# design.net
KiCad netlist of a schematic drawn in EasyEDA Pro
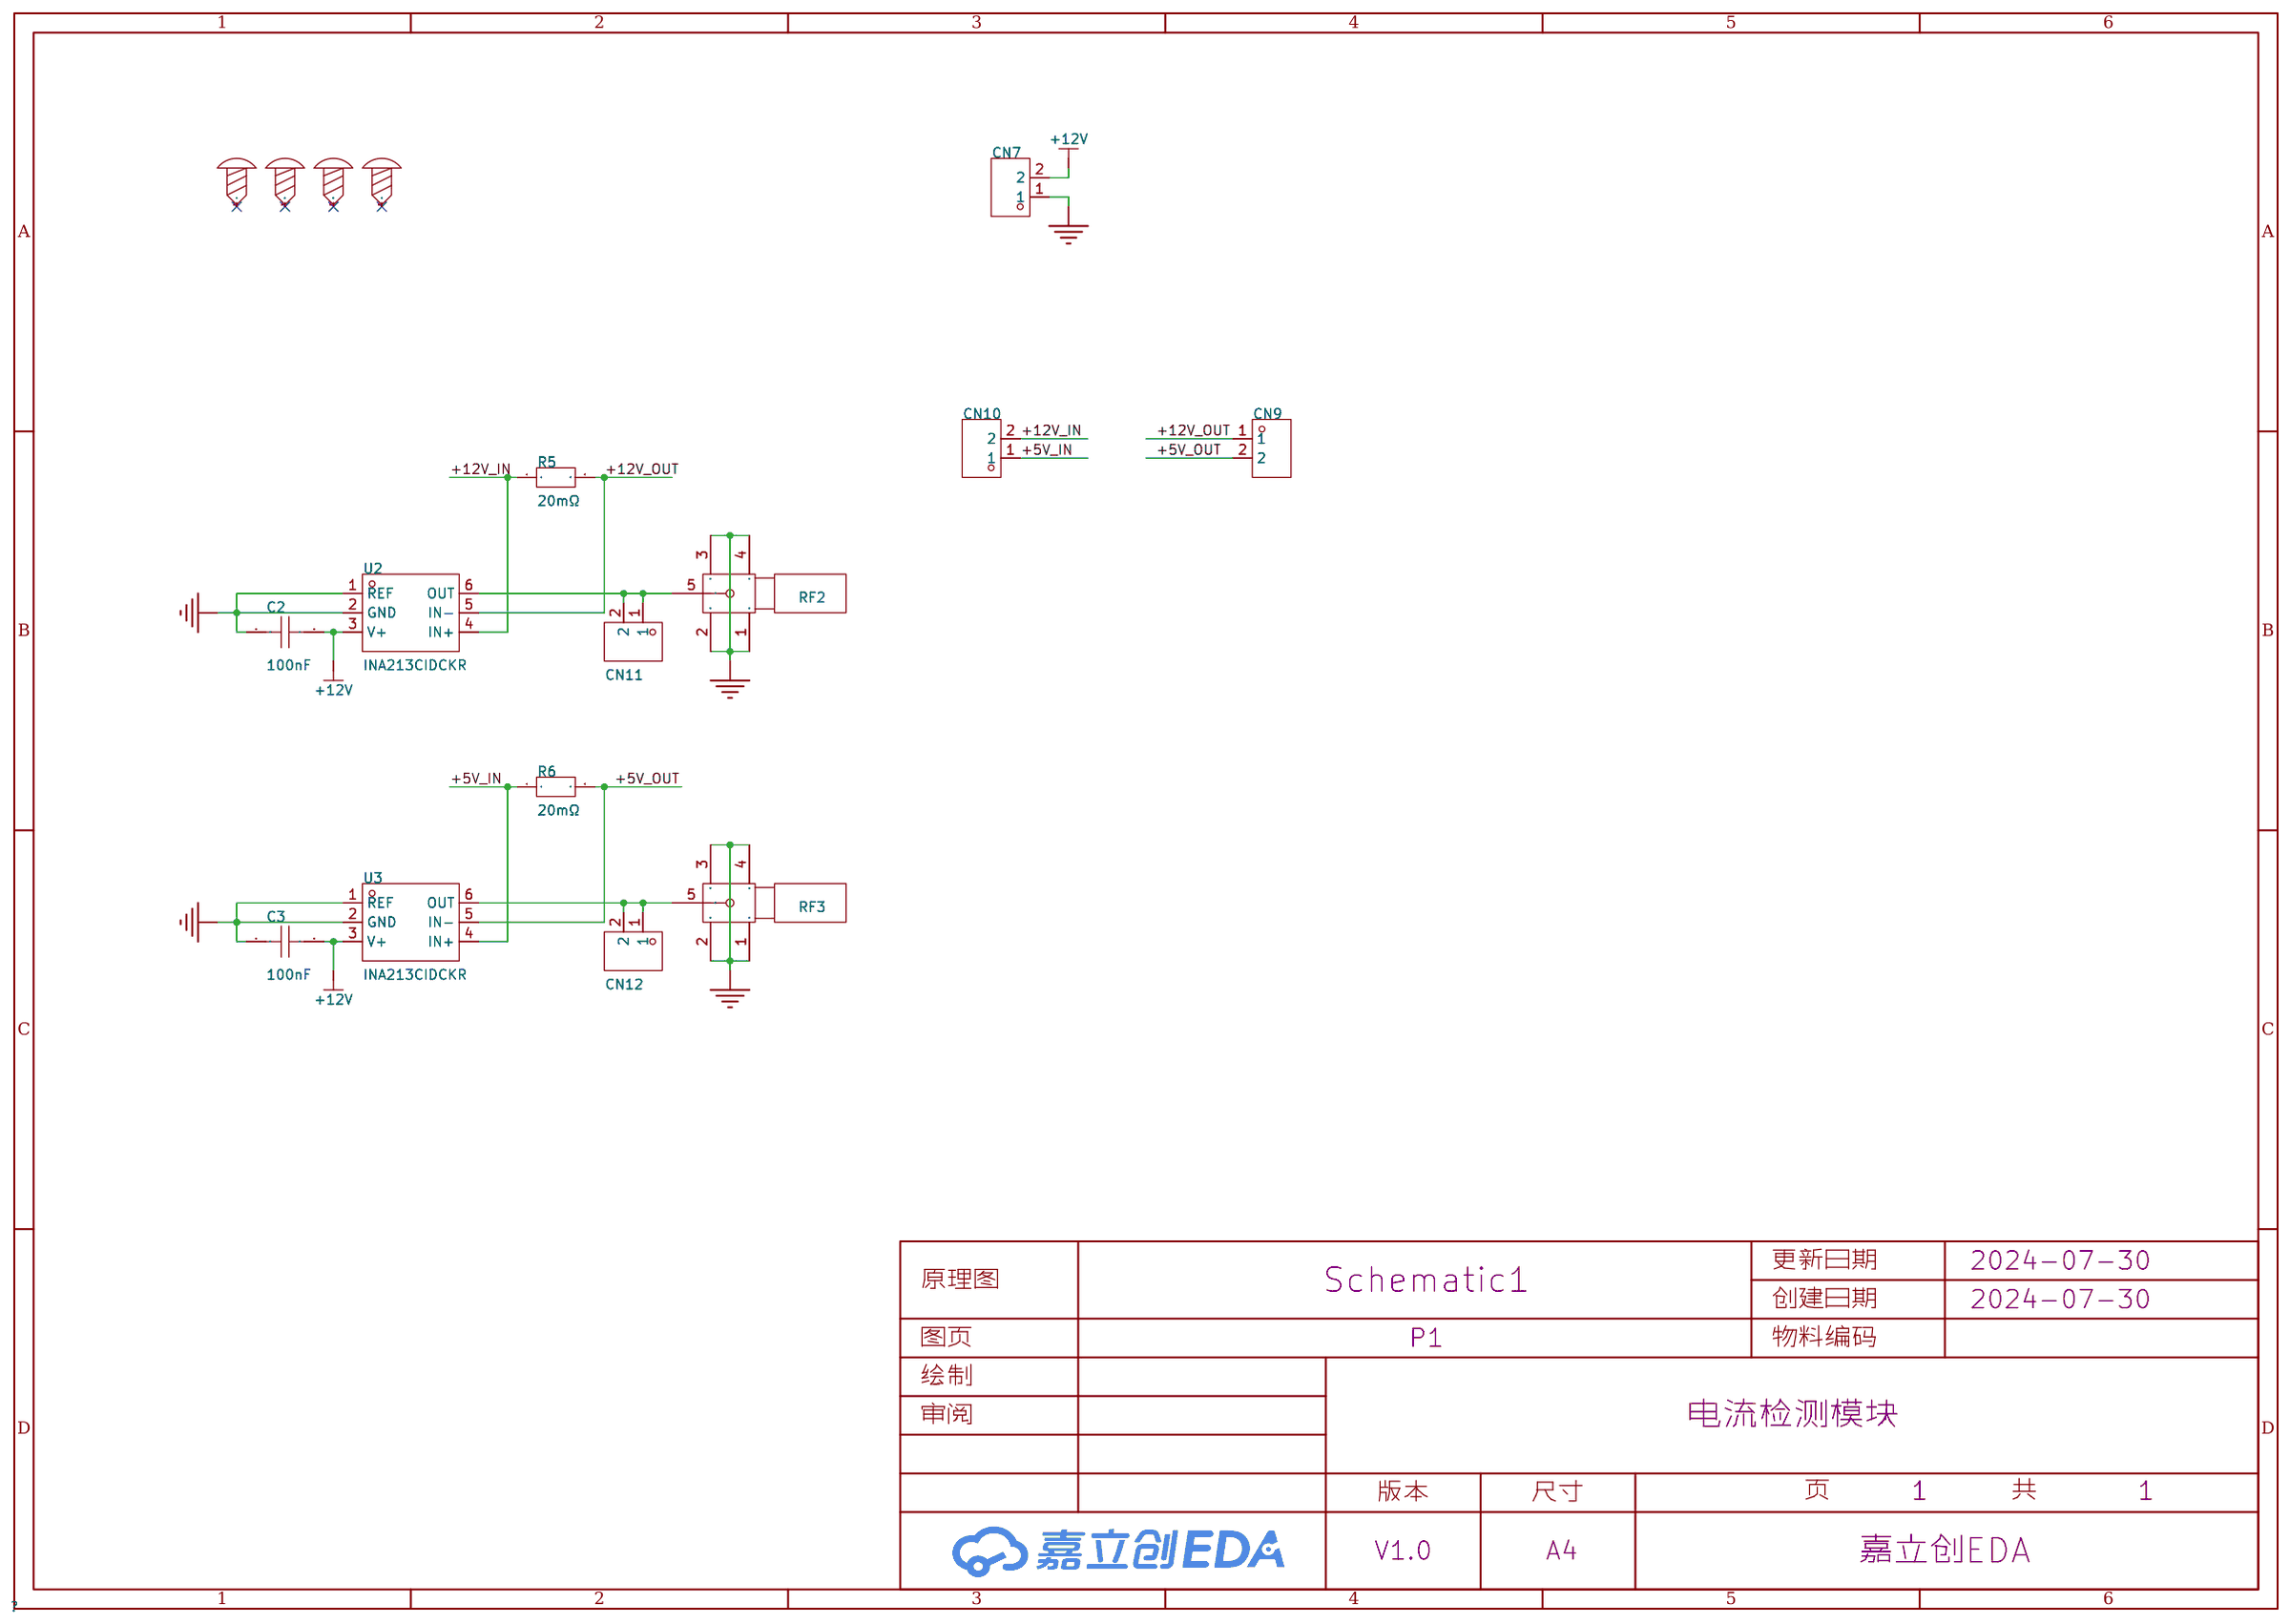
[diagram p0: schematic sheet]

(export (version "E")
  (design (tool "Eeschema 10.0.6"))
  (components
    (comp (ref "C2")
      (value "100nF")
      (footprint "easyedapro:C0603")
      (libsource (lib "easyedapro") (part "CapAcitance"))
    )
    (comp (ref "C3")
      (value "100nF")
      (footprint "easyedapro:C0603")
      (libsource (lib "easyedapro") (part "CapAcitance"))
    )
    (comp (ref "CN7")
      (value "DB2ERC-5.08-2P-GN")
      (footprint "easyedapro:CONN-TH_2P-P5.08_DB2ERC-5.08-2P")
      (fields (field (name "Manufacturer") "DORABO(地博电气)"))
      (libsource (lib "easyedapro") (part "DB2ERC-5.08-2P"))
    )
    (comp (ref "CN9")
      (value "DB2ERC-5.08-2P-GN")
      (footprint "easyedapro:CONN-TH_2P-P5.08_DB2ERC-5.08-2P")
      (fields (field (name "Manufacturer") "DORABO(地博电气)"))
      (libsource (lib "easyedapro") (part "DB2ERC-5.08-2P"))
    )
    (comp (ref "CN10")
      (value "DB2ERC-5.08-2P-GN")
      (footprint "easyedapro:CONN-TH_2P-P5.08_DB2ERC-5.08-2P")
      (fields (field (name "Manufacturer") "DORABO(地博电气)"))
      (libsource (lib "easyedapro") (part "DB2ERC-5.08-2P"))
    )
    (comp (ref "CN11")
      (value "DB2EVC-3.81-2P-GN")
      (footprint "easyedapro:CONN-TH_2P-P3.81_DB2EVC-3.81-2P-BK")
      (fields (field (name "Manufacturer") "DORABO(地博电气)"))
      (libsource (lib "easyedapro") (part "DB2EVC-3.81-2P"))
    )
    (comp (ref "CN12")
      (value "DB2EVC-3.81-2P-GN")
      (footprint "easyedapro:CONN-TH_2P-P3.81_DB2EVC-3.81-2P-BK")
      (fields (field (name "Manufacturer") "DORABO(地博电气)"))
      (libsource (lib "easyedapro") (part "DB2EVC-3.81-2P"))
    )
    (comp (ref "R5")
      (value "20mΩ")
      (footprint "easyedapro:R2512")
      (description "电阻类型:采样电阻;阻值:20mΩ;精度:±1%;功率:3W;温度系数:±100ppm/°C;安装方式:贴片;")
      (fields
        (field (name "Manufacturer Part") "HoGT2512-3W-20mR-1%")
        (field (name "Manufacturer") "Milliohm(毫欧)")
      )
      (libsource (lib "easyedapro") (part "HOGT2512-3W-20MR-1%"))
    )
    (comp (ref "R6")
      (value "20mΩ")
      (footprint "easyedapro:R2512")
      (description "电阻类型:采样电阻;阻值:20mΩ;精度:±1%;功率:3W;温度系数:±100ppm/°C;安装方式:贴片;")
      (fields
        (field (name "Manufacturer Part") "HoGT2512-3W-20mR-1%")
        (field (name "Manufacturer") "Milliohm(毫欧)")
      )
      (libsource (lib "easyedapro") (part "HOGT2512-3W-20MR-1%"))
    )
    (comp (ref "RF2")
      (value "BWSMA-KE-Z001")
      (footprint "easyedapro:SMA-TH_BWSMA-KE-Z001")
      (fields (field (name "Manufacturer") "BAT WIRELESS(蝙蝠无线)"))
      (libsource (lib "easyedapro") (part "BWSMA-KE-Z001"))
    )
    (comp (ref "RF3")
      (value "BWSMA-KE-Z001")
      (footprint "easyedapro:SMA-TH_BWSMA-KE-Z001")
      (fields (field (name "Manufacturer") "BAT WIRELESS(蝙蝠无线)"))
      (libsource (lib "easyedapro") (part "BWSMA-KE-Z001"))
    )
    (comp (ref "TP1") (value "~") (footprint "easyedapro:M3螺丝") (libsource (lib "easyedapro") (part "螺丝孔")))
    (comp (ref "TP2") (value "~") (footprint "easyedapro:M3螺丝") (libsource (lib "easyedapro") (part "螺丝孔")))
    (comp (ref "TP3") (value "~") (footprint "easyedapro:M3螺丝") (libsource (lib "easyedapro") (part "螺丝孔")))
    (comp (ref "TP4") (value "~") (footprint "easyedapro:M3螺丝") (libsource (lib "easyedapro") (part "螺丝孔")))
    (comp (ref "U2")
      (value "INA213CIDCKR")
      (footprint "easyedapro:SC70-6_L2.0-W1.3-P0.65-LS2.1-BL")
      (description "放大器数:单路;")
      (fields (field (name "Manufacturer") "TI(德州仪器)"))
      (libsource (lib "easyedapro") (part "INA213CIDCKR"))
    )
    (comp (ref "U3")
      (value "INA213CIDCKR")
      (footprint "easyedapro:SC70-6_L2.0-W1.3-P0.65-LS2.1-BL")
      (description "放大器数:单路;")
      (fields (field (name "Manufacturer") "TI(德州仪器)"))
      (libsource (lib "easyedapro") (part "INA213CIDCKR"))
    )
  )
  (nets
    (net (code "1") (name "+12V") (class "Default")
      (node (ref "C2") (pin "2") (pinfunction "2_2") (pintype "input"))
      (node (ref "C3") (pin "2") (pinfunction "2_2") (pintype "input"))
      (node (ref "CN7") (pin "2") (pinfunction "2_2") (pintype "unspecified"))
      (node (ref "U2") (pin "3") (pinfunction "V+_3") (pintype "input"))
      (node (ref "U3") (pin "3") (pinfunction "V+_3") (pintype "input"))
    )
    (net (code "2") (name "/+5V_IN") (class "Default")
      (node (ref "CN10") (pin "1") (pinfunction "1_1") (pintype "unspecified"))
      (node (ref "R6") (pin "1") (pinfunction "1_1") (pintype "unspecified"))
      (node (ref "U3") (pin "4") (pinfunction "IN+_4") (pintype "input"))
    )
    (net (code "3") (name "/+5V_OUT") (class "Default")
      (node (ref "CN9") (pin "2") (pinfunction "2_2") (pintype "unspecified"))
      (node (ref "R6") (pin "2") (pinfunction "2_2") (pintype "unspecified"))
      (node (ref "U3") (pin "5") (pinfunction "IN-_5") (pintype "input"))
    )
    (net (code "4") (name "/+12V_IN") (class "Default")
      (node (ref "CN10") (pin "2") (pinfunction "2_2") (pintype "unspecified"))
      (node (ref "R5") (pin "1") (pinfunction "1_1") (pintype "unspecified"))
      (node (ref "U2") (pin "4") (pinfunction "IN+_4") (pintype "input"))
    )
    (net (code "5") (name "/+12V_OUT") (class "Default")
      (node (ref "CN9") (pin "1") (pinfunction "1_1") (pintype "unspecified"))
      (node (ref "R5") (pin "2") (pinfunction "2_2") (pintype "unspecified"))
      (node (ref "U2") (pin "5") (pinfunction "IN-_5") (pintype "input"))
    )
    (net (code "6") (name "GND") (class "Default")
      (node (ref "C2") (pin "1") (pinfunction "1_1") (pintype "input"))
      (node (ref "C3") (pin "1") (pinfunction "1_1") (pintype "input"))
      (node (ref "CN7") (pin "1") (pinfunction "1_1") (pintype "unspecified"))
      (node (ref "RF2") (pin "1") (pinfunction "1_1") (pintype "unspecified"))
      (node (ref "RF2") (pin "2") (pinfunction "2_2") (pintype "unspecified"))
      (node (ref "RF2") (pin "3") (pinfunction "3_3") (pintype "unspecified"))
      (node (ref "RF2") (pin "4") (pinfunction "4_4") (pintype "unspecified"))
      (node (ref "RF3") (pin "1") (pinfunction "1_1") (pintype "unspecified"))
      (node (ref "RF3") (pin "2") (pinfunction "2_2") (pintype "unspecified"))
      (node (ref "RF3") (pin "3") (pinfunction "3_3") (pintype "unspecified"))
      (node (ref "RF3") (pin "4") (pinfunction "4_4") (pintype "unspecified"))
      (node (ref "U2") (pin "1") (pinfunction "REF_1") (pintype "input"))
      (node (ref "U2") (pin "2") (pinfunction "GND_2") (pintype "input"))
      (node (ref "U3") (pin "1") (pinfunction "REF_1") (pintype "input"))
      (node (ref "U3") (pin "2") (pinfunction "GND_2") (pintype "input"))
    )
    (net (code "7") (name "Net-(U2-OUT)") (class "Default")
      (node (ref "CN11") (pin "1") (pinfunction "1_1") (pintype "unspecified"))
      (node (ref "CN11") (pin "2") (pinfunction "2_2") (pintype "unspecified"))
      (node (ref "RF2") (pin "5") (pinfunction "5_5") (pintype "unspecified"))
      (node (ref "U2") (pin "6") (pinfunction "OUT_6") (pintype "input"))
    )
    (net (code "8") (name "Net-(U3-OUT)") (class "Default")
      (node (ref "CN12") (pin "1") (pinfunction "1_1") (pintype "unspecified"))
      (node (ref "CN12") (pin "2") (pinfunction "2_2") (pintype "unspecified"))
      (node (ref "RF3") (pin "5") (pinfunction "5_5") (pintype "unspecified"))
      (node (ref "U3") (pin "6") (pinfunction "OUT_6") (pintype "input"))
    )
    (net (code "9") (name "unconnected-(TP1-Pad1)") (class "Default")
      (node (ref "TP1") (pin "1") (pinfunction "1_1") (pintype "input+no_connect"))
    )
    (net (code "10") (name "unconnected-(TP2-Pad1)") (class "Default")
      (node (ref "TP2") (pin "1") (pinfunction "1_1") (pintype "input+no_connect"))
    )
    (net (code "11") (name "unconnected-(TP3-Pad1)") (class "Default")
      (node (ref "TP3") (pin "1") (pinfunction "1_1") (pintype "input+no_connect"))
    )
    (net (code "12") (name "unconnected-(TP4-Pad1)") (class "Default")
      (node (ref "TP4") (pin "1") (pinfunction "1_1") (pintype "input+no_connect"))
    )
  )
)
